# VoltageLEDs.net
KiCad netlist of a schematic drawn in Altium Designer
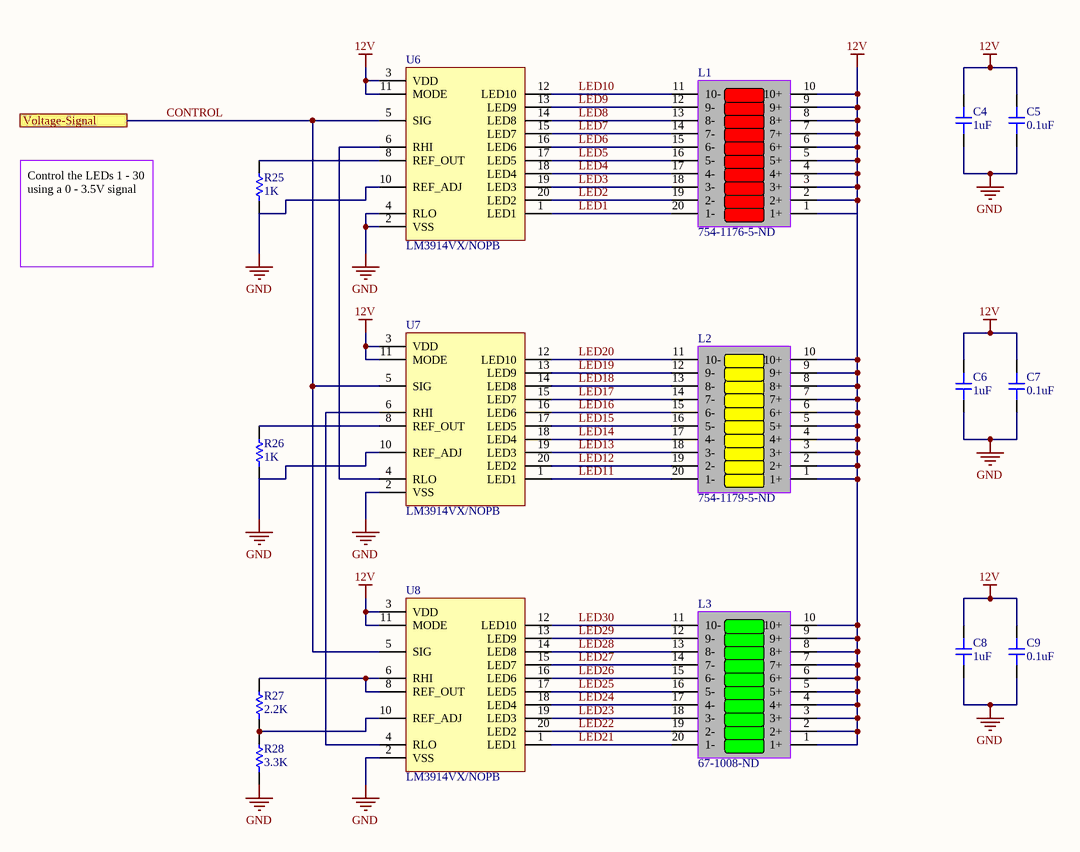
[diagram p0: VoltageLEDs.SchDoc]

(export (version "E")
  (design (tool "Eeschema 10.0.6"))
  (components
    (comp (ref "C4")
      (value "1uF")
      (footprint "CAP-0805")
      (description "CAP CER 1UF 50V X5R 0805")
      (fields
        (field (name "MANUFACTURER") "KEMET")
        (field (name "MANUFACTURER PART NUMBER") "C0805C105K5PACTU")
      )
      (libsource (lib "WorkshopSlib") (part "C0805C105K5PACTU"))
    )
    (comp (ref "C5")
      (value "0.1uF")
      (footprint "CAP-0805")
      (description "CAP CER 0.1UF 50V Y5V 0805")
      (fields
        (field (name "MANUFACTURER") "KEMET")
        (field (name "MANUFACTURER PART NUMBER") "C0805C104Z5VACTU")
      )
      (libsource (lib "WorkshopSlib") (part "C0805C104Z5VACTU"))
    )
    (comp (ref "C6")
      (value "1uF")
      (footprint "CAP-0805")
      (description "CAP CER 1UF 50V X5R 0805")
      (fields
        (field (name "MANUFACTURER") "KEMET")
        (field (name "MANUFACTURER PART NUMBER") "C0805C105K5PACTU")
      )
      (libsource (lib "WorkshopSlib") (part "C0805C105K5PACTU"))
    )
    (comp (ref "C7")
      (value "0.1uF")
      (footprint "CAP-0805")
      (description "CAP CER 0.1UF 50V Y5V 0805")
      (fields
        (field (name "MANUFACTURER") "KEMET")
        (field (name "MANUFACTURER PART NUMBER") "C0805C104Z5VACTU")
      )
      (libsource (lib "WorkshopSlib") (part "C0805C104Z5VACTU"))
    )
    (comp (ref "C8")
      (value "1uF")
      (footprint "CAP-0805")
      (description "CAP CER 1UF 50V X5R 0805")
      (fields
        (field (name "MANUFACTURER") "KEMET")
        (field (name "MANUFACTURER PART NUMBER") "C0805C105K5PACTU")
      )
      (libsource (lib "WorkshopSlib") (part "C0805C105K5PACTU"))
    )
    (comp (ref "C9")
      (value "0.1uF")
      (footprint "CAP-0805")
      (description "CAP CER 0.1UF 50V Y5V 0805")
      (fields
        (field (name "MANUFACTURER") "KEMET")
        (field (name "MANUFACTURER PART NUMBER") "C0805C104Z5VACTU")
      )
      (libsource (lib "WorkshopSlib") (part "C0805C104Z5VACTU"))
    )
    (comp (ref "L1")
      (value "754-1176-5-ND")
      (footprint "LEDBAR-10")
      (description "LED BAR GRAPH 10SEG 627NM RED")
      (fields (field (name "MANUFACTURER") "Kingbright") (field (name "MANUFACTURER PART NUMBER") "DC-10EWA"))
      (libsource (lib "WorkshopSlib") (part "754-1176-5-ND"))
    )
    (comp (ref "L2")
      (value "754-1179-5-ND")
      (footprint "LEDBAR-10")
      (description "LED BAR GRAPH 10SEG 590NM YLW")
      (fields (field (name "MANUFACTURER") "Kingbright") (field (name "MANUFACTURER PART NUMBER") "DC-10YWA"))
      (libsource (lib "LEDs") (part "LEDBAR-10-YLW"))
    )
    (comp (ref "L3")
      (value "67-1008-ND")
      (footprint "LEDBAR-10")
      (description "LED ARRAY 10X25MM 10SEG GRN DIFF")
      (fields
        (field (name "MANUFACTURER") "Lumex")
        (field (name "MANUFACTURER PART NUMBER") "SSA-LXB10GW-GF/LP")
      )
      (libsource (lib "LEDs") (part "LEDBAR-10-GRN"))
    )
    (comp (ref "R25")
      (value "1K")
      (footprint "RES-0603")
      (description "RES SMD 1K OHM 1% 1/10W 0603")
      (fields
        (field (name "MANUFACTURER") "Vishay Dale")
        (field (name "MANUFACTURER PART NUMBER") "CRCW06031K00FKEA")
      )
      (libsource (lib "Resistors") (part "0603-1KR"))
    )
    (comp (ref "R26")
      (value "1K")
      (footprint "RES-0603")
      (description "RES SMD 1K OHM 1% 1/10W 0603")
      (fields
        (field (name "MANUFACTURER") "Vishay Dale")
        (field (name "MANUFACTURER PART NUMBER") "CRCW06031K00FKEA")
      )
      (libsource (lib "Resistors") (part "0603-1KR"))
    )
    (comp (ref "R27")
      (value "2.2K")
      (footprint "RES-0603")
      (description "RES SMD 2.2K OHM 1% 1/10W 0603")
      (fields
        (field (name "MANUFACTURER") "Yageo Phycomp")
        (field (name "MANUFACTURER PART NUMBER") "RC0603FR-072K2L")
      )
      (libsource (lib "WorkshopSlib") (part "RC0603FR-072K2L"))
    )
    (comp (ref "R28")
      (value "3.3K")
      (footprint "RES-0603")
      (description "RES SMD 3.3K OHM 1% 1/10W 0603")
      (fields
        (field (name "MANUFACTURER") "Yageo Phycomp")
        (field (name "MANUFACTURER PART NUMBER") "RC0603FR-073K3L")
      )
      (libsource (lib "WorkshopSlib") (part "RC0603FR-073K3L"))
    )
    (comp (ref "U6")
      (value "LM3914VX/NOPB")
      (footprint "PLCC127P990X990X457-20N")
      (description "IC DRVR DOT/BAR DISPLAY 20PLCC")
      (fields (field (name "MANUFACTURER") "TI National Semiconductor"))
      (libsource (lib "WorkshopSlib") (part "LM3914VX/NOPB"))
    )
    (comp (ref "U7")
      (value "LM3914VX/NOPB")
      (footprint "PLCC127P990X990X457-20N")
      (description "IC DRVR DOT/BAR DISPLAY 20PLCC")
      (fields (field (name "MANUFACTURER") "TI National Semiconductor"))
      (libsource (lib "WorkshopSlib") (part "LM3914VX/NOPB"))
    )
    (comp (ref "U8")
      (value "LM3914VX/NOPB")
      (footprint "PLCC127P990X990X457-20N")
      (description "IC DRVR DOT/BAR DISPLAY 20PLCC")
      (fields (field (name "MANUFACTURER") "TI National Semiconductor"))
      (libsource (lib "WorkshopSlib") (part "LM3914VX/NOPB"))
    )
  )
  (nets
    (net (code "1") (name "/CONTROL") (class "Default")
      (node (ref "U6") (pin "5") (pinfunction "SIG_5") (pintype "passive"))
      (node (ref "U7") (pin "5") (pinfunction "SIG_5") (pintype "passive"))
      (node (ref "U8") (pin "5") (pinfunction "SIG_5") (pintype "passive"))
    )
    (net (code "2") (name "/LED1") (class "Default")
      (node (ref "L1") (pin "20") (pinfunction "1-_20") (pintype "passive"))
      (node (ref "U6") (pin "1") (pinfunction "LED1_1") (pintype "passive"))
    )
    (net (code "3") (name "/LED2") (class "Default")
      (node (ref "L1") (pin "19") (pinfunction "2-_19") (pintype "passive"))
      (node (ref "U6") (pin "20") (pinfunction "LED2_20") (pintype "passive"))
    )
    (net (code "4") (name "/LED3") (class "Default")
      (node (ref "L1") (pin "18") (pinfunction "3-_18") (pintype "passive"))
      (node (ref "U6") (pin "19") (pinfunction "LED3_19") (pintype "passive"))
    )
    (net (code "5") (name "/LED4") (class "Default")
      (node (ref "L1") (pin "17") (pinfunction "4-_17") (pintype "passive"))
      (node (ref "U6") (pin "18") (pinfunction "LED4_18") (pintype "passive"))
    )
    (net (code "6") (name "/LED5") (class "Default")
      (node (ref "L1") (pin "16") (pinfunction "5-_16") (pintype "passive"))
      (node (ref "U6") (pin "17") (pinfunction "LED5_17") (pintype "passive"))
    )
    (net (code "7") (name "/LED6") (class "Default")
      (node (ref "L1") (pin "15") (pinfunction "6-_15") (pintype "passive"))
      (node (ref "U6") (pin "16") (pinfunction "LED6_16") (pintype "passive"))
    )
    (net (code "8") (name "/LED7") (class "Default")
      (node (ref "L1") (pin "14") (pinfunction "7-_14") (pintype "passive"))
      (node (ref "U6") (pin "15") (pinfunction "LED7_15") (pintype "passive"))
    )
    (net (code "9") (name "/LED8") (class "Default")
      (node (ref "L1") (pin "13") (pinfunction "8-_13") (pintype "passive"))
      (node (ref "U6") (pin "14") (pinfunction "LED8_14") (pintype "passive"))
    )
    (net (code "10") (name "/LED9") (class "Default")
      (node (ref "L1") (pin "12") (pinfunction "9-_12") (pintype "passive"))
      (node (ref "U6") (pin "13") (pinfunction "LED9_13") (pintype "passive"))
    )
    (net (code "11") (name "/LED10") (class "Default")
      (node (ref "L1") (pin "11") (pinfunction "10-_11") (pintype "passive"))
      (node (ref "U6") (pin "12") (pinfunction "LED10_12") (pintype "passive"))
    )
    (net (code "12") (name "/LED11") (class "Default")
      (node (ref "L2") (pin "20") (pinfunction "1-_20") (pintype "passive"))
      (node (ref "U7") (pin "1") (pinfunction "LED1_1") (pintype "passive"))
    )
    (net (code "13") (name "/LED12") (class "Default")
      (node (ref "L2") (pin "19") (pinfunction "2-_19") (pintype "passive"))
      (node (ref "U7") (pin "20") (pinfunction "LED2_20") (pintype "passive"))
    )
    (net (code "14") (name "/LED13") (class "Default")
      (node (ref "L2") (pin "18") (pinfunction "3-_18") (pintype "passive"))
      (node (ref "U7") (pin "19") (pinfunction "LED3_19") (pintype "passive"))
    )
    (net (code "15") (name "/LED14") (class "Default")
      (node (ref "L2") (pin "17") (pinfunction "4-_17") (pintype "passive"))
      (node (ref "U7") (pin "18") (pinfunction "LED4_18") (pintype "passive"))
    )
    (net (code "16") (name "/LED15") (class "Default")
      (node (ref "L2") (pin "16") (pinfunction "5-_16") (pintype "passive"))
      (node (ref "U7") (pin "17") (pinfunction "LED5_17") (pintype "passive"))
    )
    (net (code "17") (name "/LED16") (class "Default")
      (node (ref "L2") (pin "15") (pinfunction "6-_15") (pintype "passive"))
      (node (ref "U7") (pin "16") (pinfunction "LED6_16") (pintype "passive"))
    )
    (net (code "18") (name "/LED17") (class "Default")
      (node (ref "L2") (pin "14") (pinfunction "7-_14") (pintype "passive"))
      (node (ref "U7") (pin "15") (pinfunction "LED7_15") (pintype "passive"))
    )
    (net (code "19") (name "/LED18") (class "Default")
      (node (ref "L2") (pin "13") (pinfunction "8-_13") (pintype "passive"))
      (node (ref "U7") (pin "14") (pinfunction "LED8_14") (pintype "passive"))
    )
    (net (code "20") (name "/LED19") (class "Default")
      (node (ref "L2") (pin "12") (pinfunction "9-_12") (pintype "passive"))
      (node (ref "U7") (pin "13") (pinfunction "LED9_13") (pintype "passive"))
    )
    (net (code "21") (name "/LED20") (class "Default")
      (node (ref "L2") (pin "11") (pinfunction "10-_11") (pintype "passive"))
      (node (ref "U7") (pin "12") (pinfunction "LED10_12") (pintype "passive"))
    )
    (net (code "22") (name "/LED21") (class "Default")
      (node (ref "L3") (pin "20") (pinfunction "1-_20") (pintype "passive"))
      (node (ref "U8") (pin "1") (pinfunction "LED1_1") (pintype "passive"))
    )
    (net (code "23") (name "/LED22") (class "Default")
      (node (ref "L3") (pin "19") (pinfunction "2-_19") (pintype "passive"))
      (node (ref "U8") (pin "20") (pinfunction "LED2_20") (pintype "passive"))
    )
    (net (code "24") (name "/LED23") (class "Default")
      (node (ref "L3") (pin "18") (pinfunction "3-_18") (pintype "passive"))
      (node (ref "U8") (pin "19") (pinfunction "LED3_19") (pintype "passive"))
    )
    (net (code "25") (name "/LED24") (class "Default")
      (node (ref "L3") (pin "17") (pinfunction "4-_17") (pintype "passive"))
      (node (ref "U8") (pin "18") (pinfunction "LED4_18") (pintype "passive"))
    )
    (net (code "26") (name "/LED25") (class "Default")
      (node (ref "L3") (pin "16") (pinfunction "5-_16") (pintype "passive"))
      (node (ref "U8") (pin "17") (pinfunction "LED5_17") (pintype "passive"))
    )
    (net (code "27") (name "/LED26") (class "Default")
      (node (ref "L3") (pin "15") (pinfunction "6-_15") (pintype "passive"))
      (node (ref "U8") (pin "16") (pinfunction "LED6_16") (pintype "passive"))
    )
    (net (code "28") (name "/LED27") (class "Default")
      (node (ref "L3") (pin "14") (pinfunction "7-_14") (pintype "passive"))
      (node (ref "U8") (pin "15") (pinfunction "LED7_15") (pintype "passive"))
    )
    (net (code "29") (name "/LED28") (class "Default")
      (node (ref "L3") (pin "13") (pinfunction "8-_13") (pintype "passive"))
      (node (ref "U8") (pin "14") (pinfunction "LED8_14") (pintype "passive"))
    )
    (net (code "30") (name "/LED29") (class "Default")
      (node (ref "L3") (pin "12") (pinfunction "9-_12") (pintype "passive"))
      (node (ref "U8") (pin "13") (pinfunction "LED9_13") (pintype "passive"))
    )
    (net (code "31") (name "/LED30") (class "Default")
      (node (ref "L3") (pin "11") (pinfunction "10-_11") (pintype "passive"))
      (node (ref "U8") (pin "12") (pinfunction "LED10_12") (pintype "passive"))
    )
    (net (code "32") (name "12V") (class "Default")
      (node (ref "C4") (pin "2") (pinfunction "2_2") (pintype "passive"))
      (node (ref "C5") (pin "2") (pinfunction "2_2") (pintype "passive"))
      (node (ref "C6") (pin "2") (pinfunction "2_2") (pintype "passive"))
      (node (ref "C7") (pin "2") (pinfunction "2_2") (pintype "passive"))
      (node (ref "C8") (pin "2") (pinfunction "2_2") (pintype "passive"))
      (node (ref "C9") (pin "2") (pinfunction "2_2") (pintype "passive"))
      (node (ref "L1") (pin "1") (pinfunction "1+_1") (pintype "passive"))
      (node (ref "L1") (pin "10") (pinfunction "10+_10") (pintype "passive"))
      (node (ref "L1") (pin "2") (pinfunction "2+_2") (pintype "passive"))
      (node (ref "L1") (pin "3") (pinfunction "3+_3") (pintype "passive"))
      (node (ref "L1") (pin "4") (pinfunction "4+_4") (pintype "passive"))
      (node (ref "L1") (pin "5") (pinfunction "5+_5") (pintype "passive"))
      (node (ref "L1") (pin "6") (pinfunction "6+_6") (pintype "passive"))
      (node (ref "L1") (pin "7") (pinfunction "7+_7") (pintype "passive"))
      (node (ref "L1") (pin "8") (pinfunction "8+_8") (pintype "passive"))
      (node (ref "L1") (pin "9") (pinfunction "9+_9") (pintype "passive"))
      (node (ref "L2") (pin "1") (pinfunction "1+_1") (pintype "passive"))
      (node (ref "L2") (pin "10") (pinfunction "10+_10") (pintype "passive"))
      (node (ref "L2") (pin "2") (pinfunction "2+_2") (pintype "passive"))
      (node (ref "L2") (pin "3") (pinfunction "3+_3") (pintype "passive"))
      (node (ref "L2") (pin "4") (pinfunction "4+_4") (pintype "passive"))
      (node (ref "L2") (pin "5") (pinfunction "5+_5") (pintype "passive"))
      (node (ref "L2") (pin "6") (pinfunction "6+_6") (pintype "passive"))
      (node (ref "L2") (pin "7") (pinfunction "7+_7") (pintype "passive"))
      (node (ref "L2") (pin "8") (pinfunction "8+_8") (pintype "passive"))
      (node (ref "L2") (pin "9") (pinfunction "9+_9") (pintype "passive"))
      (node (ref "L3") (pin "1") (pinfunction "1+_1") (pintype "passive"))
      (node (ref "L3") (pin "10") (pinfunction "10+_10") (pintype "passive"))
      (node (ref "L3") (pin "2") (pinfunction "2+_2") (pintype "passive"))
      (node (ref "L3") (pin "3") (pinfunction "3+_3") (pintype "passive"))
      (node (ref "L3") (pin "4") (pinfunction "4+_4") (pintype "passive"))
      (node (ref "L3") (pin "5") (pinfunction "5+_5") (pintype "passive"))
      (node (ref "L3") (pin "6") (pinfunction "6+_6") (pintype "passive"))
      (node (ref "L3") (pin "7") (pinfunction "7+_7") (pintype "passive"))
      (node (ref "L3") (pin "8") (pinfunction "8+_8") (pintype "passive"))
      (node (ref "L3") (pin "9") (pinfunction "9+_9") (pintype "passive"))
      (node (ref "U6") (pin "11") (pinfunction "MODE_11") (pintype "passive"))
      (node (ref "U6") (pin "3") (pinfunction "VDD_3") (pintype "passive"))
      (node (ref "U7") (pin "11") (pinfunction "MODE_11") (pintype "passive"))
      (node (ref "U7") (pin "3") (pinfunction "VDD_3") (pintype "passive"))
      (node (ref "U8") (pin "11") (pinfunction "MODE_11") (pintype "passive"))
      (node (ref "U8") (pin "3") (pinfunction "VDD_3") (pintype "passive"))
    )
    (net (code "33") (name "GND") (class "Default")
      (node (ref "C4") (pin "1") (pinfunction "1_1") (pintype "passive"))
      (node (ref "C5") (pin "1") (pinfunction "1_1") (pintype "passive"))
      (node (ref "C6") (pin "1") (pinfunction "1_1") (pintype "passive"))
      (node (ref "C7") (pin "1") (pinfunction "1_1") (pintype "passive"))
      (node (ref "C8") (pin "1") (pinfunction "1_1") (pintype "passive"))
      (node (ref "C9") (pin "1") (pinfunction "1_1") (pintype "passive"))
      (node (ref "R25") (pin "1") (pinfunction "1_1") (pintype "passive"))
      (node (ref "R26") (pin "1") (pinfunction "1_1") (pintype "passive"))
      (node (ref "R28") (pin "1") (pinfunction "1_1") (pintype "passive"))
      (node (ref "U6") (pin "10") (pinfunction "REF_ADJ_10") (pintype "passive"))
      (node (ref "U6") (pin "2") (pinfunction "VSS_2") (pintype "passive"))
      (node (ref "U6") (pin "4") (pinfunction "RLO_4") (pintype "passive"))
      (node (ref "U7") (pin "10") (pinfunction "REF_ADJ_10") (pintype "passive"))
      (node (ref "U7") (pin "2") (pinfunction "VSS_2") (pintype "passive"))
      (node (ref "U8") (pin "2") (pinfunction "VSS_2") (pintype "passive"))
    )
    (net (code "34") (name "Net-(U6-REF_OUT)") (class "Default")
      (node (ref "R25") (pin "2") (pinfunction "2_2") (pintype "passive"))
      (node (ref "U6") (pin "8") (pinfunction "REF_OUT_8") (pintype "passive"))
    )
    (net (code "35") (name "Net-(U6-RHI)") (class "Default")
      (node (ref "U6") (pin "6") (pinfunction "RHI_6") (pintype "passive"))
      (node (ref "U7") (pin "4") (pinfunction "RLO_4") (pintype "passive"))
    )
    (net (code "36") (name "Net-(U7-REF_OUT)") (class "Default")
      (node (ref "R26") (pin "2") (pinfunction "2_2") (pintype "passive"))
      (node (ref "U7") (pin "8") (pinfunction "REF_OUT_8") (pintype "passive"))
    )
    (net (code "37") (name "Net-(U7-RHI)") (class "Default")
      (node (ref "U7") (pin "6") (pinfunction "RHI_6") (pintype "passive"))
      (node (ref "U8") (pin "4") (pinfunction "RLO_4") (pintype "passive"))
    )
    (net (code "38") (name "Net-(U8-REF_ADJ)") (class "Default")
      (node (ref "R27") (pin "1") (pinfunction "1_1") (pintype "passive"))
      (node (ref "R28") (pin "2") (pinfunction "2_2") (pintype "passive"))
      (node (ref "U8") (pin "10") (pinfunction "REF_ADJ_10") (pintype "passive"))
    )
    (net (code "39") (name "Net-(U8-REF_OUT)") (class "Default")
      (node (ref "R27") (pin "2") (pinfunction "2_2") (pintype "passive"))
      (node (ref "U8") (pin "6") (pinfunction "RHI_6") (pintype "passive"))
      (node (ref "U8") (pin "8") (pinfunction "REF_OUT_8") (pintype "passive"))
    )
  )
)
